# Logic_Level_Converter.net
KiCad netlist of a schematic drawn in EAGLE
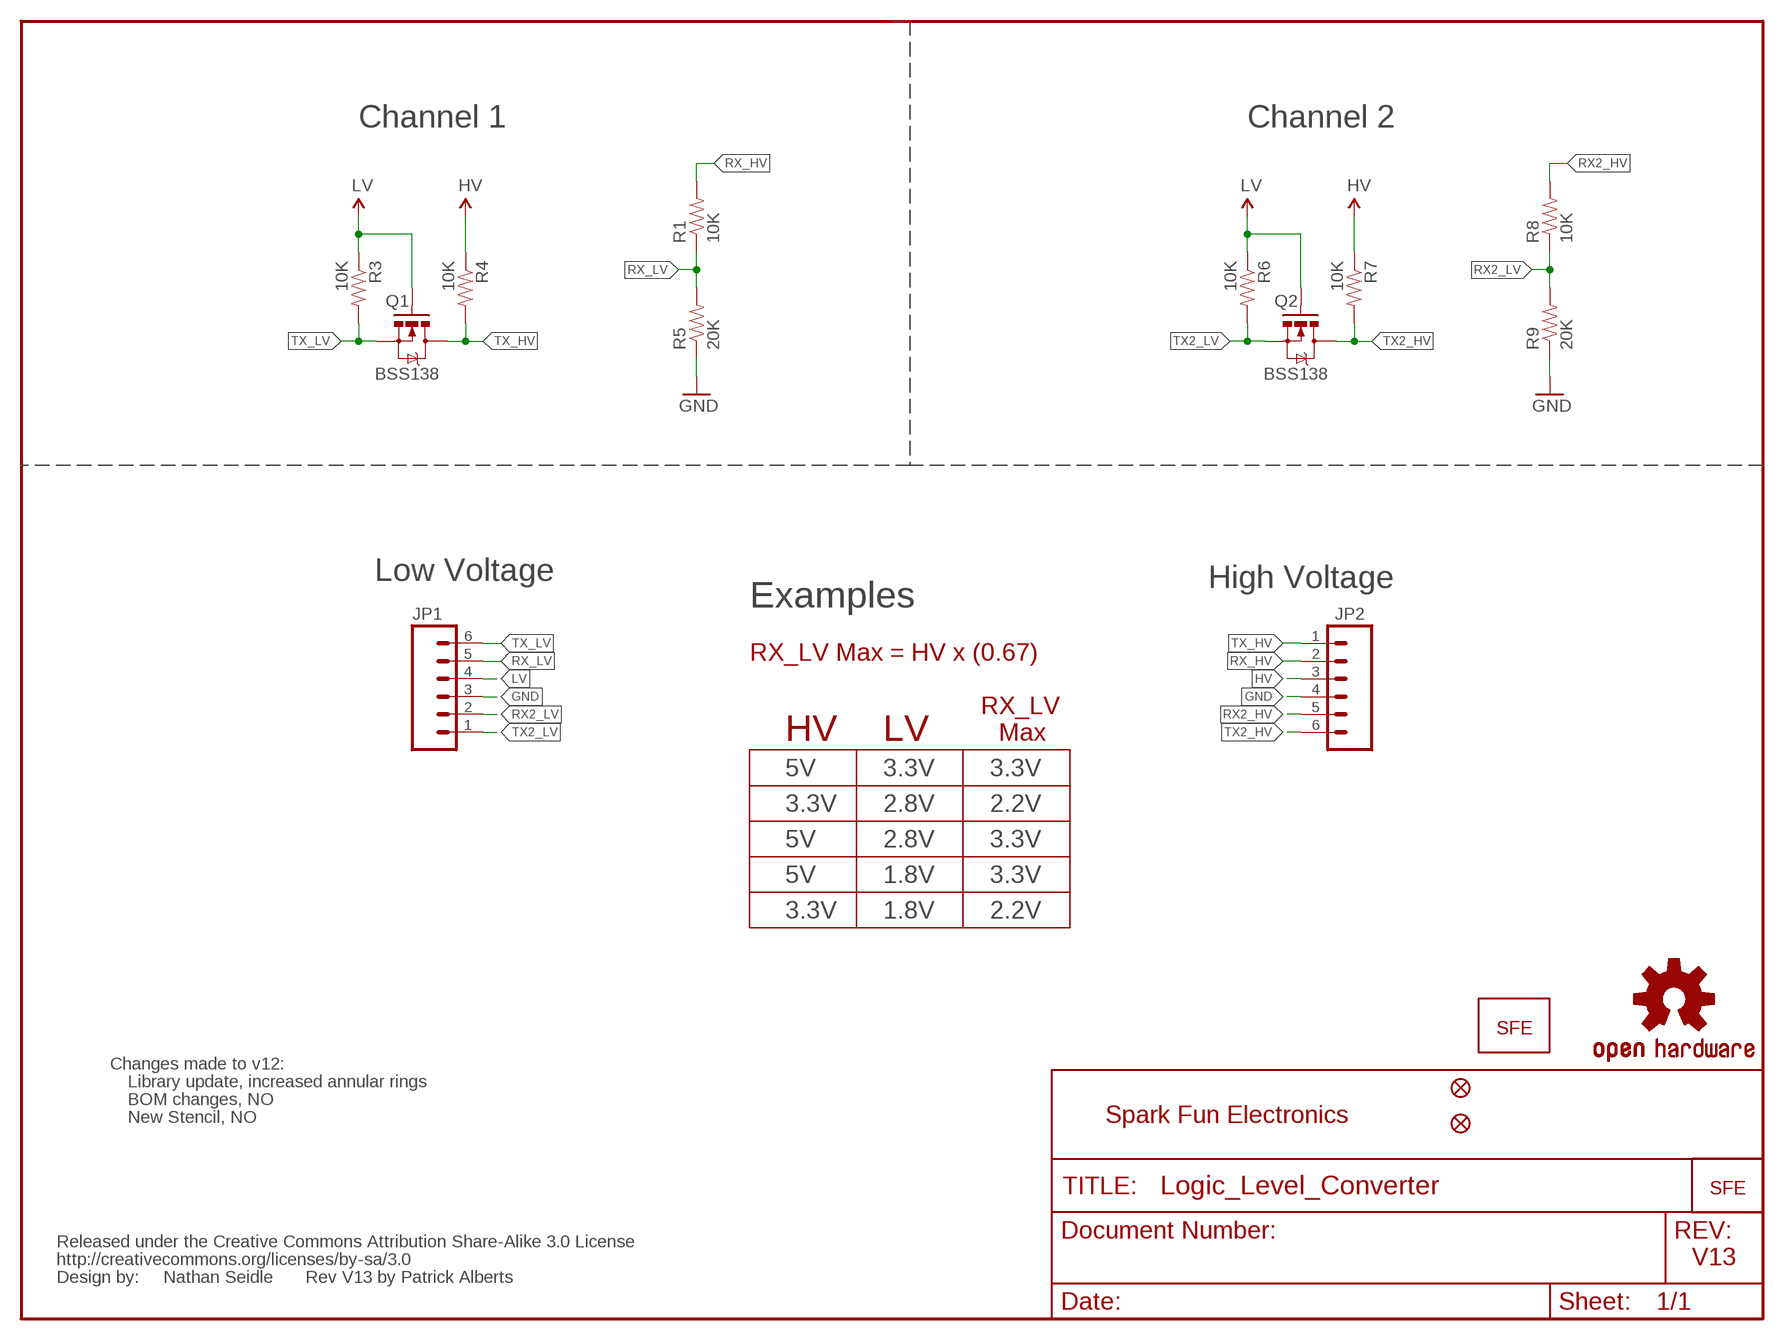
[diagram p0: schematic, sheet 1]

(export (version "E")
  (design (tool "Eeschema 10.0.6"))
  (components
    (comp (ref "CC_TEXT1")
      (value "CREATIVE_COMMONS")
      (footprint "eagle-import:CREATIVE_COMMONS")
      (libsource (lib "eagle-import") (part "CREATIVE_COMMONS"))
    )
    (comp (ref "JP1")
      (value "M06SIP")
      (footprint "eagle-import:1X06")
      (libsource (lib "eagle-import") (part "M06SIP"))
    )
    (comp (ref "JP2")
      (value "M06SIP")
      (footprint "eagle-import:1X06")
      (libsource (lib "eagle-import") (part "M06SIP"))
    )
    (comp (ref "JP3")
      (value "FIDUCIALUFIDUCIAL")
      (footprint "eagle-import:MICRO-FIDUCIAL")
      (libsource (lib "eagle-import") (part "FIDUCIALUFIDUCIAL"))
    )
    (comp (ref "JP4")
      (value "FIDUCIALUFIDUCIAL")
      (footprint "eagle-import:MICRO-FIDUCIAL")
      (libsource (lib "eagle-import") (part "FIDUCIALUFIDUCIAL"))
    )
    (comp (ref "JP5")
      (value "LOGO-SFENW2")
      (footprint "eagle-import:SFE-NEW-WEB")
      (libsource (lib "eagle-import") (part "SparkFun-Aesthetics_LOGO-SFENW2"))
    )
    (comp (ref "Q1")
      (value "BSS138")
      (footprint "eagle-import:SOT23-3")
      (libsource (lib "eagle-import") (part "MOSFET-NCHANNELSMD"))
    )
    (comp (ref "Q2")
      (value "BSS138")
      (footprint "eagle-import:SOT23-3")
      (libsource (lib "eagle-import") (part "MOSFET-NCHANNELSMD"))
    )
    (comp (ref "R1")
      (value "10K")
      (footprint "eagle-import:0603-RES")
      (libsource (lib "eagle-import") (part "RESISTOR0603-RES"))
    )
    (comp (ref "R3")
      (value "10K")
      (footprint "eagle-import:0603-RES")
      (libsource (lib "eagle-import") (part "RESISTOR0603-RES"))
    )
    (comp (ref "R4")
      (value "10K")
      (footprint "eagle-import:0603-RES")
      (libsource (lib "eagle-import") (part "RESISTOR0603-RES"))
    )
    (comp (ref "R5")
      (value "20K")
      (footprint "eagle-import:0603-RES")
      (libsource (lib "eagle-import") (part "RESISTOR0603-RES"))
    )
    (comp (ref "R6")
      (value "10K")
      (footprint "eagle-import:0603-RES")
      (libsource (lib "eagle-import") (part "RESISTOR0603-RES"))
    )
    (comp (ref "R7")
      (value "10K")
      (footprint "eagle-import:0603-RES")
      (libsource (lib "eagle-import") (part "RESISTOR0603-RES"))
    )
    (comp (ref "R8")
      (value "10K")
      (footprint "eagle-import:0603-RES")
      (libsource (lib "eagle-import") (part "RESISTOR0603-RES"))
    )
    (comp (ref "R9")
      (value "20K")
      (footprint "eagle-import:0603-RES")
      (libsource (lib "eagle-import") (part "RESISTOR0603-RES"))
    )
    (comp (ref "U$1")
      (value "LOGO-SFESK")
      (footprint "eagle-import:SFE-LOGO-FLAME")
      (libsource (lib "eagle-import") (part "LOGO-SFESK"))
    )
    (comp (ref "U$2")
      (value "OSHW-LOGOS")
      (footprint "eagle-import:OSHW-LOGO-S")
      (libsource (lib "eagle-import") (part "OSHW-LOGOS"))
    )
  )
  (nets
    (net (code "1") (name "GND") (class "Default")
      (node (ref "JP1") (pin "3") (pinfunction "3_3") (pintype "passive"))
      (node (ref "JP2") (pin "4") (pinfunction "4_4") (pintype "passive"))
      (node (ref "R5") (pin "1") (pinfunction "1_1") (pintype "passive"))
      (node (ref "R9") (pin "1") (pinfunction "1_1") (pintype "passive"))
    )
    (net (code "2") (name "HV") (class "Default")
      (node (ref "JP2") (pin "3") (pinfunction "3_3") (pintype "passive"))
      (node (ref "R4") (pin "1") (pinfunction "1_1") (pintype "passive"))
      (node (ref "R7") (pin "1") (pinfunction "1_1") (pintype "passive"))
    )
    (net (code "3") (name "LV") (class "Default")
      (node (ref "JP1") (pin "4") (pinfunction "4_4") (pintype "passive"))
      (node (ref "Q1") (pin "1") (pinfunction "G_1") (pintype "passive"))
      (node (ref "Q2") (pin "1") (pinfunction "G_1") (pintype "passive"))
      (node (ref "R3") (pin "1") (pinfunction "1_1") (pintype "passive"))
      (node (ref "R6") (pin "1") (pinfunction "1_1") (pintype "passive"))
    )
    (net (code "4") (name "RX2_HV") (class "Default")
      (node (ref "JP2") (pin "5") (pinfunction "5_5") (pintype "passive"))
      (node (ref "R8") (pin "2") (pinfunction "2_2") (pintype "passive"))
    )
    (net (code "5") (name "RX2_LV") (class "Default")
      (node (ref "JP1") (pin "2") (pinfunction "2_2") (pintype "passive"))
      (node (ref "R8") (pin "1") (pinfunction "1_1") (pintype "passive"))
      (node (ref "R9") (pin "2") (pinfunction "2_2") (pintype "passive"))
    )
    (net (code "6") (name "RX_HV") (class "Default")
      (node (ref "JP2") (pin "2") (pinfunction "2_2") (pintype "passive"))
      (node (ref "R1") (pin "2") (pinfunction "2_2") (pintype "passive"))
    )
    (net (code "7") (name "RX_LV") (class "Default")
      (node (ref "JP1") (pin "5") (pinfunction "5_5") (pintype "passive"))
      (node (ref "R1") (pin "1") (pinfunction "1_1") (pintype "passive"))
      (node (ref "R5") (pin "2") (pinfunction "2_2") (pintype "passive"))
    )
    (net (code "8") (name "TX2_HV") (class "Default")
      (node (ref "JP2") (pin "6") (pinfunction "6_6") (pintype "passive"))
      (node (ref "Q2") (pin "3") (pinfunction "D_3") (pintype "passive"))
      (node (ref "R7") (pin "2") (pinfunction "2_2") (pintype "passive"))
    )
    (net (code "9") (name "TX2_LV") (class "Default")
      (node (ref "JP1") (pin "1") (pinfunction "1_1") (pintype "passive"))
      (node (ref "Q2") (pin "2") (pinfunction "S_2") (pintype "passive"))
      (node (ref "R6") (pin "2") (pinfunction "2_2") (pintype "passive"))
    )
    (net (code "10") (name "TX_HV") (class "Default")
      (node (ref "JP2") (pin "1") (pinfunction "1_1") (pintype "passive"))
      (node (ref "Q1") (pin "3") (pinfunction "D_3") (pintype "passive"))
      (node (ref "R4") (pin "2") (pinfunction "2_2") (pintype "passive"))
    )
    (net (code "11") (name "TX_LV") (class "Default")
      (node (ref "JP1") (pin "6") (pinfunction "6_6") (pintype "passive"))
      (node (ref "Q1") (pin "2") (pinfunction "S_2") (pintype "passive"))
      (node (ref "R3") (pin "2") (pinfunction "2_2") (pintype "passive"))
    )
  )
)
